# Quarfinder_rev2.net
KiCad netlist of a schematic drawn in EAGLE
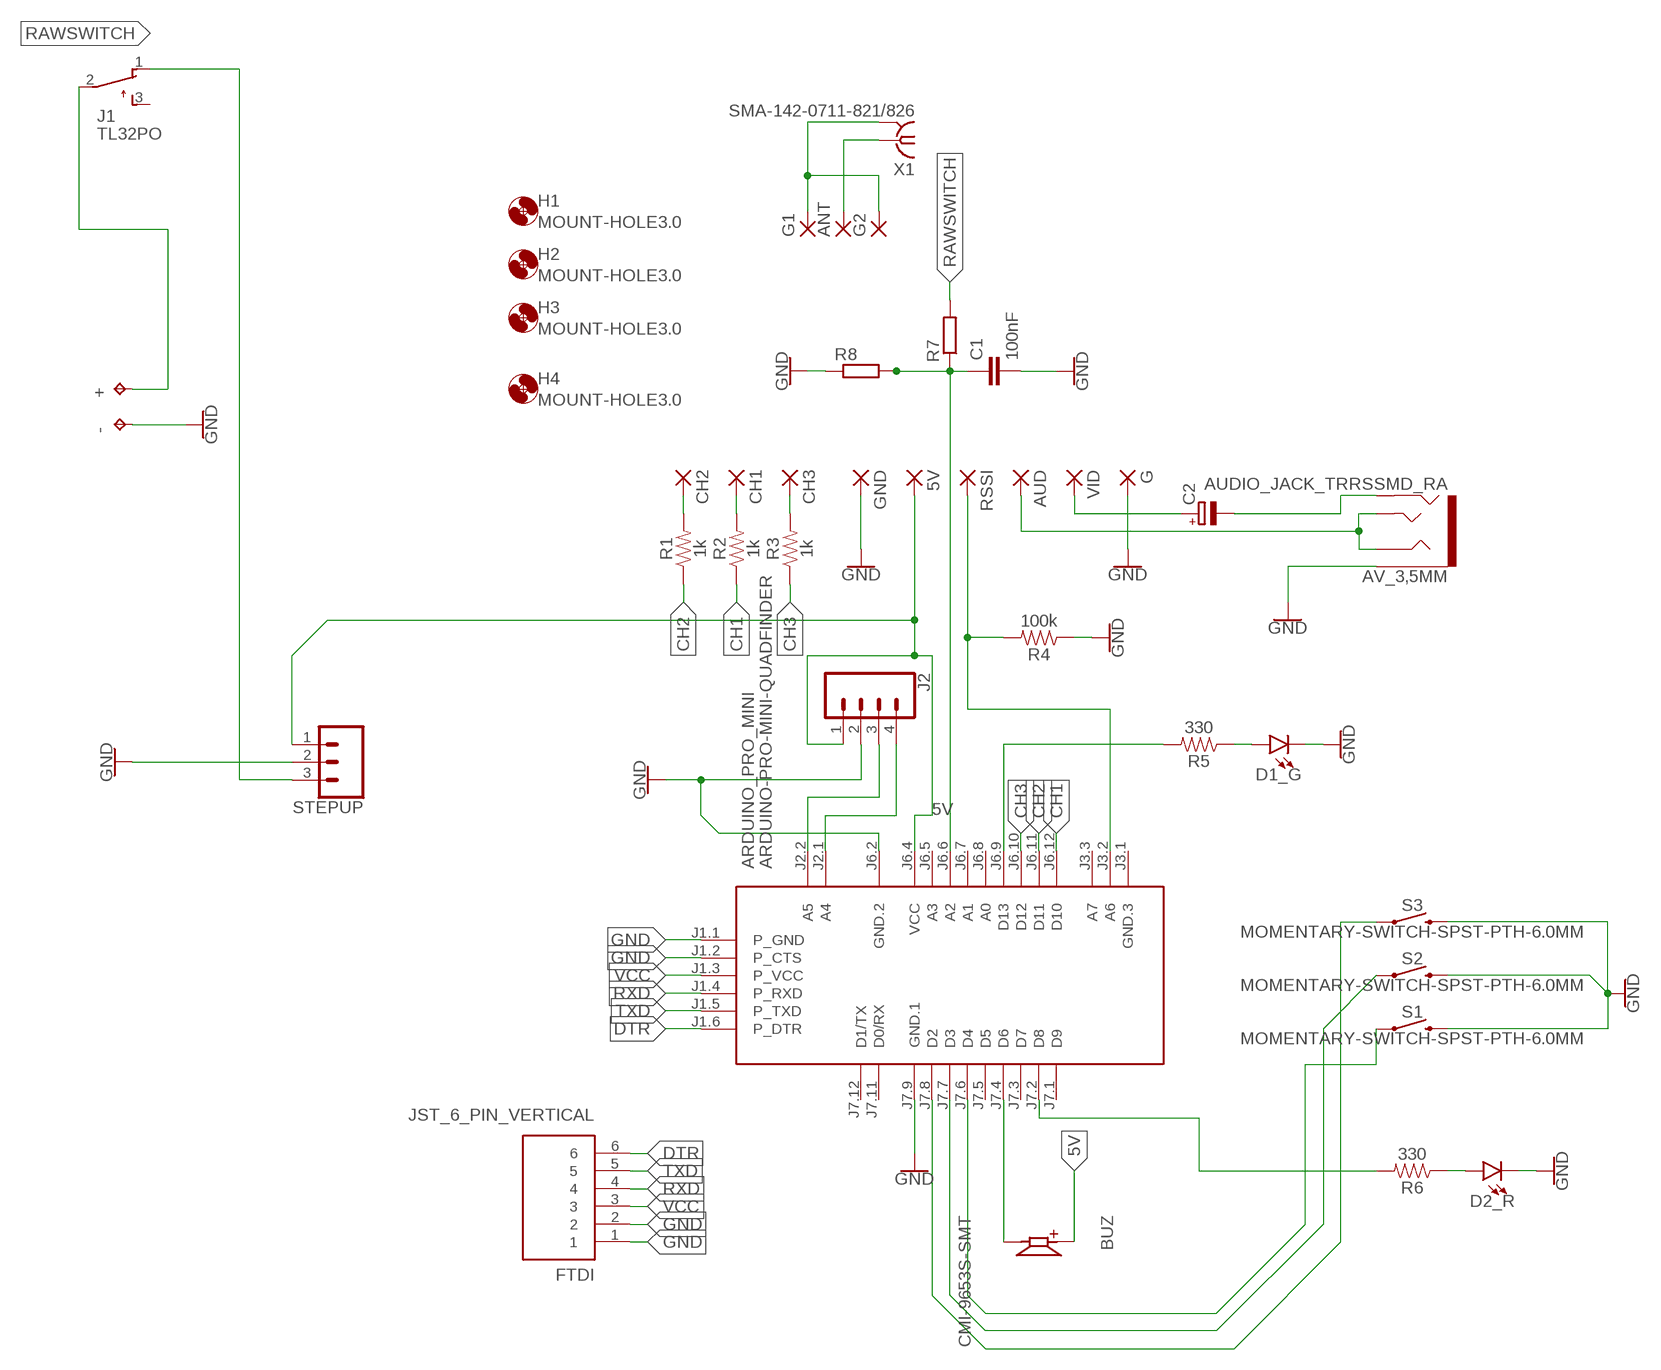
[diagram p0: schematic, sheet 1]

(export (version "E")
  (design (tool "Eeschema 10.0.6"))
  (components
    (comp (ref "+")
      (value "TPTP20R")
      (footprint "eagle-import:TP20R")
      (libsource (lib "eagle-import") (part "TPTP20R"))
    )
    (comp (ref "-")
      (value "TPTP20R")
      (footprint "eagle-import:TP20R")
      (libsource (lib "eagle-import") (part "TPTP20R"))
    )
    (comp (ref "5V")
      (value "SMD2")
      (footprint "eagle-import:SMD1,27-2,54")
      (libsource (lib "eagle-import") (part "SMD2"))
    )
    (comp (ref "ANT")
      (value "SMD2")
      (footprint "eagle-import:SMD1,27-2,54")
      (libsource (lib "eagle-import") (part "SMD2"))
    )
    (comp (ref "ARDUINO_PRO_MINI")
      (value "ARDUINO-PRO-MINI-QUADFINDER")
      (footprint "eagle-import:ARDUINO-PRO-MINI")
      (libsource (lib "eagle-import") (part "ARDUINO-PRO-MINI-QUADFINDER"))
    )
    (comp (ref "AUD")
      (value "SMD2")
      (footprint "eagle-import:SMD1,27-2,54")
      (libsource (lib "eagle-import") (part "SMD2"))
    )
    (comp (ref "AV_3,5MM")
      (value "AUDIO_JACK_TRRSSMD_RA")
      (footprint "eagle-import:AUDIO_JACK_3.5MM_TRRS_SMD_RA")
      (libsource (lib "eagle-import") (part "AUDIO_JACK_TRRSSMD_RA"))
    )
    (comp (ref "BUZ")
      (value "CMI-9653S-SMT")
      (footprint "eagle-import:CUI_CMI-9653S-SMT")
      (fields (field (name "MF") "CUI Inc.") (field (name "MP") "CMI-9653S-SMT-TR"))
      (libsource (lib "eagle-import") (part "CMI-9653S-SMT"))
    )
    (comp (ref "C1")
      (value "100nF")
      (footprint "eagle-import:0603")
      (libsource (lib "eagle-import") (part "1.0UF-0603-16V-10%"))
    )
    (comp (ref "C2")
      (value "CPOL-EUD/7343-31R")
      (footprint "eagle-import:D_7343-31R")
      (libsource (lib "eagle-import") (part "CPOL-EUD/7343-31R"))
    )
    (comp (ref "CH1")
      (value "SMD2")
      (footprint "eagle-import:SMD1,27-2,54")
      (libsource (lib "eagle-import") (part "SMD2"))
    )
    (comp (ref "CH2")
      (value "SMD2")
      (footprint "eagle-import:SMD1,27-2,54")
      (libsource (lib "eagle-import") (part "SMD2"))
    )
    (comp (ref "CH3")
      (value "SMD2")
      (footprint "eagle-import:SMD1,27-2,54")
      (libsource (lib "eagle-import") (part "SMD2"))
    )
    (comp (ref "D1_G")
      (value "LED1206")
      (footprint "eagle-import:LED-1206")
      (libsource (lib "eagle-import") (part "LED1206"))
    )
    (comp (ref "D2_R")
      (value "LED1206")
      (footprint "eagle-import:LED-1206")
      (libsource (lib "eagle-import") (part "LED1206"))
    )
    (comp (ref "FTDI")
      (value "JST_6_PIN_VERTICAL")
      (footprint "eagle-import:JST-6-SMD-VERT-1.0MM")
      (libsource (lib "eagle-import") (part "JST_6_PIN_VERTICAL"))
    )
    (comp (ref "G")
      (value "SMD2")
      (footprint "eagle-import:SMD1,27-2,54")
      (libsource (lib "eagle-import") (part "SMD2"))
    )
    (comp (ref "G1")
      (value "SMD2")
      (footprint "eagle-import:SMD1,27-2,54")
      (libsource (lib "eagle-import") (part "SMD2"))
    )
    (comp (ref "G2")
      (value "SMD2")
      (footprint "eagle-import:SMD1,27-2,54")
      (libsource (lib "eagle-import") (part "SMD2"))
    )
    (comp (ref "GND")
      (value "SMD2")
      (footprint "eagle-import:SMD1,27-2,54")
      (libsource (lib "eagle-import") (part "SMD2"))
    )
    (comp (ref "H1")
      (value "MOUNT-HOLE3.0")
      (footprint "eagle-import:3,0")
      (libsource (lib "eagle-import") (part "MOUNT-HOLE3.0"))
    )
    (comp (ref "H2")
      (value "MOUNT-HOLE3.0")
      (footprint "eagle-import:3,0")
      (libsource (lib "eagle-import") (part "MOUNT-HOLE3.0"))
    )
    (comp (ref "H3")
      (value "MOUNT-HOLE3.0")
      (footprint "eagle-import:3,0")
      (libsource (lib "eagle-import") (part "MOUNT-HOLE3.0"))
    )
    (comp (ref "H4")
      (value "MOUNT-HOLE3.0")
      (footprint "eagle-import:3,0")
      (libsource (lib "eagle-import") (part "MOUNT-HOLE3.0"))
    )
    (comp (ref "J1")
      (value "TL32PO")
      (footprint "eagle-import:TL3XPO")
      (libsource (lib "eagle-import") (part "TL32PO"))
    )
    (comp (ref "J2")
      (value "CONN_04")
      (footprint "eagle-import:1X04")
      (libsource (lib "eagle-import") (part "CONN_04"))
    )
    (comp (ref "R1")
      (value "1k")
      (footprint "eagle-import:0603")
      (libsource (lib "eagle-import") (part "1KOHM-0603-1/10W-1%"))
    )
    (comp (ref "R2")
      (value "1k")
      (footprint "eagle-import:0603")
      (libsource (lib "eagle-import") (part "1KOHM-0603-1/10W-1%"))
    )
    (comp (ref "R3")
      (value "1k")
      (footprint "eagle-import:0603")
      (libsource (lib "eagle-import") (part "1KOHM-0603-1/10W-1%"))
    )
    (comp (ref "R4")
      (value "100k")
      (footprint "eagle-import:0603")
      (libsource (lib "eagle-import") (part "1KOHM-0603-1/10W-1%"))
    )
    (comp (ref "R5")
      (value "330")
      (footprint "eagle-import:0603")
      (libsource (lib "eagle-import") (part "1KOHM-0603-1/10W-1%"))
    )
    (comp (ref "R6")
      (value "330")
      (footprint "eagle-import:0603")
      (libsource (lib "eagle-import") (part "1KOHM-0603-1/10W-1%"))
    )
    (comp (ref "R7")
      (value "R-EU_R1206")
      (footprint "eagle-import:R1206")
      (libsource (lib "eagle-import") (part "R-EU_R1206"))
    )
    (comp (ref "R8")
      (value "R-EU_R1206")
      (footprint "eagle-import:R1206")
      (libsource (lib "eagle-import") (part "R-EU_R1206"))
    )
    (comp (ref "RSSI")
      (value "SMD2")
      (footprint "eagle-import:SMD1,27-2,54")
      (libsource (lib "eagle-import") (part "SMD2"))
    )
    (comp (ref "S1")
      (value "MOMENTARY-SWITCH-SPST-PTH-6.0MM")
      (footprint "eagle-import:TACTILE_SWITCH_PTH_6.0MM")
      (libsource (lib "eagle-import") (part "MOMENTARY-SWITCH-SPST-PTH-6.0MM"))
    )
    (comp (ref "S2")
      (value "MOMENTARY-SWITCH-SPST-PTH-6.0MM")
      (footprint "eagle-import:TACTILE_SWITCH_PTH_6.0MM")
      (libsource (lib "eagle-import") (part "MOMENTARY-SWITCH-SPST-PTH-6.0MM"))
    )
    (comp (ref "S3")
      (value "MOMENTARY-SWITCH-SPST-PTH-6.0MM")
      (footprint "eagle-import:TACTILE_SWITCH_PTH_6.0MM")
      (libsource (lib "eagle-import") (part "MOMENTARY-SWITCH-SPST-PTH-6.0MM"))
    )
    (comp (ref "STEPUP")
      (value "CONN_03")
      (footprint "eagle-import:1X03")
      (libsource (lib "eagle-import") (part "CONN_03"))
    )
    (comp (ref "VID")
      (value "SMD2")
      (footprint "eagle-import:SMD1,27-2,54")
      (libsource (lib "eagle-import") (part "SMD2"))
    )
    (comp (ref "X1")
      (value "SMA-142-0711-821/826")
      (footprint "eagle-import:J502-ND-142-0711-821_826")
      (fields (field (name "MF") "JOHNSON COMPONENTS") (field (name "MPN") "142-0711-821"))
      (libsource (lib "eagle-import") (part "SMA-142-0711-821/826"))
    )
  )
  (nets
    (net (code "1") (name "5V") (class "Default")
      (node (ref "5V") (pin "1") (pinfunction "P_1") (pintype "passive"))
      (node (ref "ARDUINO_PRO_MINI") (pin "J6.4") (pinfunction "VCC_J6.4") (pintype "power_in"))
      (node (ref "BUZ") (pin "P") (pinfunction "P_P") (pintype "passive"))
      (node (ref "J2") (pin "1") (pinfunction "1_1") (pintype "passive"))
      (node (ref "STEPUP") (pin "1") (pinfunction "1_1") (pintype "passive"))
    )
    (net (code "2") (name "CH1") (class "Default")
      (node (ref "ARDUINO_PRO_MINI") (pin "J6.12") (pinfunction "D10_J6.12") (pintype "bidirectional"))
      (node (ref "R2") (pin "1") (pinfunction "1_1") (pintype "passive"))
    )
    (net (code "3") (name "CH2") (class "Default")
      (node (ref "ARDUINO_PRO_MINI") (pin "J6.11") (pinfunction "D11_J6.11") (pintype "bidirectional"))
      (node (ref "R1") (pin "1") (pinfunction "1_1") (pintype "passive"))
    )
    (net (code "4") (name "CH3") (class "Default")
      (node (ref "ARDUINO_PRO_MINI") (pin "J6.10") (pinfunction "D12_J6.10") (pintype "bidirectional"))
      (node (ref "R3") (pin "1") (pinfunction "1_1") (pintype "passive"))
    )
    (net (code "5") (name "DTR") (class "Default")
      (node (ref "ARDUINO_PRO_MINI") (pin "J1.6") (pinfunction "P_DTR_J1.6") (pintype "bidirectional"))
      (node (ref "FTDI") (pin "6") (pinfunction "6_6") (pintype "bidirectional"))
    )
    (net (code "6") (name "GND") (class "Default")
      (node (ref "-") (pin "TP") (pinfunction "TP_TP") (pintype "input"))
      (node (ref "ARDUINO_PRO_MINI") (pin "J1.1") (pinfunction "P_GND_J1.1") (pintype "bidirectional"))
      (node (ref "ARDUINO_PRO_MINI") (pin "J1.2") (pinfunction "P_CTS_J1.2") (pintype "bidirectional"))
      (node (ref "ARDUINO_PRO_MINI") (pin "J6.2") (pinfunction "GND.2_J6.2") (pintype "power_in"))
      (node (ref "ARDUINO_PRO_MINI") (pin "J7.9") (pinfunction "GND.1_J7.9") (pintype "power_in"))
      (node (ref "AV_3,5MM") (pin "EARTH") (pinfunction "EARTH_EARTH") (pintype "bidirectional"))
      (node (ref "C1") (pin "2") (pinfunction "2_2") (pintype "passive"))
      (node (ref "D1_G") (pin "C") (pinfunction "C_C") (pintype "passive"))
      (node (ref "D2_R") (pin "C") (pinfunction "C_C") (pintype "passive"))
      (node (ref "FTDI") (pin "1") (pinfunction "1_1") (pintype "bidirectional"))
      (node (ref "FTDI") (pin "2") (pinfunction "2_2") (pintype "bidirectional"))
      (node (ref "G") (pin "1") (pinfunction "P_1") (pintype "passive"))
      (node (ref "G1") (pin "1") (pinfunction "P_1") (pintype "passive"))
      (node (ref "G2") (pin "1") (pinfunction "P_1") (pintype "passive"))
      (node (ref "GND") (pin "1") (pinfunction "P_1") (pintype "passive"))
      (node (ref "J2") (pin "2") (pinfunction "2_2") (pintype "passive"))
      (node (ref "R4") (pin "1") (pinfunction "1_1") (pintype "passive"))
      (node (ref "R8") (pin "1") (pinfunction "1_1") (pintype "passive"))
      (node (ref "S1") (pin "3") (pinfunction "2_3") (pintype "passive"))
      (node (ref "S2") (pin "3") (pinfunction "2_3") (pintype "passive"))
      (node (ref "S3") (pin "3") (pinfunction "2_3") (pintype "passive"))
      (node (ref "STEPUP") (pin "2") (pinfunction "2_2") (pintype "passive"))
      (node (ref "X1") (pin "G@1") (pinfunction "2_G@1") (pintype "passive"))
      (node (ref "X1") (pin "G@2") (pinfunction "2_G@2") (pintype "passive"))
      (node (ref "X1") (pin "G@3") (pinfunction "2_G@3") (pintype "passive"))
      (node (ref "X1") (pin "G@4") (pinfunction "2_G@4") (pintype "passive"))
    )
    (net (code "7") (name "Net-(ANT-P)") (class "Default")
      (node (ref "ANT") (pin "1") (pinfunction "P_1") (pintype "passive"))
      (node (ref "X1") (pin "1") (pinfunction "1_1") (pintype "passive"))
    )
    (net (code "8") (name "Net-(ARDUINO_PRO_MINI-A2)") (class "Default")
      (node (ref "ARDUINO_PRO_MINI") (pin "J6.6") (pinfunction "A2_J6.6") (pintype "bidirectional"))
      (node (ref "C1") (pin "1") (pinfunction "1_1") (pintype "passive"))
      (node (ref "R7") (pin "1") (pinfunction "1_1") (pintype "passive"))
      (node (ref "R8") (pin "2") (pinfunction "2_2") (pintype "passive"))
    )
    (net (code "9") (name "Net-(ARDUINO_PRO_MINI-A4)") (class "Default")
      (node (ref "ARDUINO_PRO_MINI") (pin "J2.1") (pinfunction "A4_J2.1") (pintype "bidirectional"))
      (node (ref "J2") (pin "4") (pinfunction "4_4") (pintype "passive"))
    )
    (net (code "10") (name "Net-(ARDUINO_PRO_MINI-A5)") (class "Default")
      (node (ref "ARDUINO_PRO_MINI") (pin "J2.2") (pinfunction "A5_J2.2") (pintype "bidirectional"))
      (node (ref "J2") (pin "3") (pinfunction "3_3") (pintype "passive"))
    )
    (net (code "11") (name "Net-(ARDUINO_PRO_MINI-A6)") (class "Default")
      (node (ref "ARDUINO_PRO_MINI") (pin "J3.2") (pinfunction "A6_J3.2") (pintype "bidirectional"))
      (node (ref "R4") (pin "2") (pinfunction "2_2") (pintype "passive"))
      (node (ref "RSSI") (pin "1") (pinfunction "P_1") (pintype "passive"))
    )
    (net (code "12") (name "Net-(ARDUINO_PRO_MINI-D2)") (class "Default")
      (node (ref "ARDUINO_PRO_MINI") (pin "J7.8") (pinfunction "D2_J7.8") (pintype "bidirectional"))
      (node (ref "S3") (pin "1") (pinfunction "1_1") (pintype "passive"))
    )
    (net (code "13") (name "Net-(ARDUINO_PRO_MINI-D3)") (class "Default")
      (node (ref "ARDUINO_PRO_MINI") (pin "J7.7") (pinfunction "D3_J7.7") (pintype "bidirectional"))
      (node (ref "S2") (pin "1") (pinfunction "1_1") (pintype "passive"))
    )
    (net (code "14") (name "Net-(ARDUINO_PRO_MINI-D4)") (class "Default")
      (node (ref "ARDUINO_PRO_MINI") (pin "J7.6") (pinfunction "D4_J7.6") (pintype "bidirectional"))
      (node (ref "S1") (pin "1") (pinfunction "1_1") (pintype "passive"))
    )
    (net (code "15") (name "Net-(ARDUINO_PRO_MINI-D6)") (class "Default")
      (node (ref "ARDUINO_PRO_MINI") (pin "J7.4") (pinfunction "D6_J7.4") (pintype "bidirectional"))
      (node (ref "BUZ") (pin "N") (pinfunction "N_N") (pintype "passive"))
    )
    (net (code "16") (name "Net-(ARDUINO_PRO_MINI-D8)") (class "Default")
      (node (ref "ARDUINO_PRO_MINI") (pin "J7.2") (pinfunction "D8_J7.2") (pintype "bidirectional"))
      (node (ref "R6") (pin "2") (pinfunction "2_2") (pintype "passive"))
    )
    (net (code "17") (name "Net-(ARDUINO_PRO_MINI-D13)") (class "Default")
      (node (ref "ARDUINO_PRO_MINI") (pin "J6.9") (pinfunction "D13_J6.9") (pintype "bidirectional"))
      (node (ref "R5") (pin "2") (pinfunction "2_2") (pintype "passive"))
    )
    (net (code "18") (name "Net-(AUD-P)") (class "Default")
      (node (ref "AUD") (pin "1") (pinfunction "P_1") (pintype "passive"))
      (node (ref "AV_3,5MM") (pin "RING1") (pinfunction "RING1_RING1") (pintype "bidirectional"))
      (node (ref "AV_3,5MM") (pin "TIP") (pinfunction "TIP_TIP") (pintype "bidirectional"))
    )
    (net (code "19") (name "Net-(AV_3,5MM-PadRING2)") (class "Default")
      (node (ref "AV_3,5MM") (pin "RING2") (pinfunction "RING2_RING2") (pintype "bidirectional"))
      (node (ref "C2") (pin "-") (pinfunction "-_-") (pintype "passive"))
    )
    (net (code "20") (name "Net-(CH1-P)") (class "Default")
      (node (ref "CH1") (pin "1") (pinfunction "P_1") (pintype "passive"))
      (node (ref "R2") (pin "2") (pinfunction "2_2") (pintype "passive"))
    )
    (net (code "21") (name "Net-(CH2-P)") (class "Default")
      (node (ref "CH2") (pin "1") (pinfunction "P_1") (pintype "passive"))
      (node (ref "R1") (pin "2") (pinfunction "2_2") (pintype "passive"))
    )
    (net (code "22") (name "Net-(CH3-P)") (class "Default")
      (node (ref "CH3") (pin "1") (pinfunction "P_1") (pintype "passive"))
      (node (ref "R3") (pin "2") (pinfunction "2_2") (pintype "passive"))
    )
    (net (code "23") (name "Net-(D1_G-PadA)") (class "Default")
      (node (ref "D1_G") (pin "A") (pinfunction "A_A") (pintype "passive"))
      (node (ref "R5") (pin "1") (pinfunction "1_1") (pintype "passive"))
    )
    (net (code "24") (name "Net-(D2_R-PadA)") (class "Default")
      (node (ref "D2_R") (pin "A") (pinfunction "A_A") (pintype "passive"))
      (node (ref "R6") (pin "1") (pinfunction "1_1") (pintype "passive"))
    )
    (net (code "25") (name "Net-(J1-P)") (class "Default")
      (node (ref "+") (pin "TP") (pinfunction "TP_TP") (pintype "input"))
      (node (ref "J1") (pin "2") (pinfunction "P_2") (pintype "passive"))
    )
    (net (code "26") (name "Net-(VID-P)") (class "Default")
      (node (ref "C2") (pin "+") (pinfunction "+_+") (pintype "passive"))
      (node (ref "VID") (pin "1") (pinfunction "P_1") (pintype "passive"))
    )
    (net (code "27") (name "RAWSWITCH") (class "Default")
      (node (ref "J1") (pin "1") (pinfunction "O_1") (pintype "passive"))
      (node (ref "R7") (pin "2") (pinfunction "2_2") (pintype "passive"))
      (node (ref "STEPUP") (pin "3") (pinfunction "3_3") (pintype "passive"))
    )
    (net (code "28") (name "RXD") (class "Default")
      (node (ref "ARDUINO_PRO_MINI") (pin "J1.4") (pinfunction "P_RXD_J1.4") (pintype "bidirectional"))
      (node (ref "FTDI") (pin "4") (pinfunction "4_4") (pintype "bidirectional"))
    )
    (net (code "29") (name "TXD") (class "Default")
      (node (ref "ARDUINO_PRO_MINI") (pin "J1.5") (pinfunction "P_TXD_J1.5") (pintype "bidirectional"))
      (node (ref "FTDI") (pin "5") (pinfunction "5_5") (pintype "bidirectional"))
    )
    (net (code "30") (name "VCC") (class "Default")
      (node (ref "ARDUINO_PRO_MINI") (pin "J1.3") (pinfunction "P_VCC_J1.3") (pintype "bidirectional"))
      (node (ref "FTDI") (pin "3") (pinfunction "3_3") (pintype "bidirectional"))
    )
    (net (code "31") (name "unconnected-(ARDUINO_PRO_MINI-A0-PadJ6.8)") (class "Default")
      (node (ref "ARDUINO_PRO_MINI") (pin "J6.8") (pinfunction "A0_J6.8") (pintype "bidirectional"))
    )
    (net (code "32") (name "unconnected-(ARDUINO_PRO_MINI-A1-PadJ6.7)") (class "Default")
      (node (ref "ARDUINO_PRO_MINI") (pin "J6.7") (pinfunction "A1_J6.7") (pintype "bidirectional"))
    )
    (net (code "33") (name "unconnected-(ARDUINO_PRO_MINI-A3-PadJ6.5)") (class "Default")
      (node (ref "ARDUINO_PRO_MINI") (pin "J6.5") (pinfunction "A3_J6.5") (pintype "bidirectional"))
    )
    (net (code "34") (name "unconnected-(ARDUINO_PRO_MINI-A7-PadJ3.3)") (class "Default")
      (node (ref "ARDUINO_PRO_MINI") (pin "J3.3") (pinfunction "A7_J3.3") (pintype "bidirectional"))
    )
    (net (code "35") (name "unconnected-(ARDUINO_PRO_MINI-D0{slash}RX-PadJ7.11)") (class "Default")
      (node (ref "ARDUINO_PRO_MINI") (pin "J7.11") (pinfunction "D0/RX_J7.11") (pintype "bidirectional"))
    )
    (net (code "36") (name "unconnected-(ARDUINO_PRO_MINI-D1{slash}TX-PadJ7.12)") (class "Default")
      (node (ref "ARDUINO_PRO_MINI") (pin "J7.12") (pinfunction "D1/TX_J7.12") (pintype "bidirectional"))
    )
    (net (code "37") (name "unconnected-(ARDUINO_PRO_MINI-D5-PadJ7.5)") (class "Default")
      (node (ref "ARDUINO_PRO_MINI") (pin "J7.5") (pinfunction "D5_J7.5") (pintype "bidirectional"))
    )
    (net (code "38") (name "unconnected-(ARDUINO_PRO_MINI-D7-PadJ7.3)") (class "Default")
      (node (ref "ARDUINO_PRO_MINI") (pin "J7.3") (pinfunction "D7_J7.3") (pintype "bidirectional"))
    )
    (net (code "39") (name "unconnected-(ARDUINO_PRO_MINI-D9-PadJ7.1)") (class "Default")
      (node (ref "ARDUINO_PRO_MINI") (pin "J7.1") (pinfunction "D9_J7.1") (pintype "bidirectional"))
    )
    (net (code "40") (name "unconnected-(ARDUINO_PRO_MINI-GND.3-PadJ3.1)") (class "Default")
      (node (ref "ARDUINO_PRO_MINI") (pin "J3.1") (pinfunction "GND.3_J3.1") (pintype "bidirectional"))
    )
    (net (code "41") (name "unconnected-(J1-S-Pad3)") (class "Default")
      (node (ref "J1") (pin "3") (pinfunction "S_3") (pintype "passive"))
    )
  )
)
